# DC_link_input.net
KiCad netlist of a schematic drawn in Altium Designer
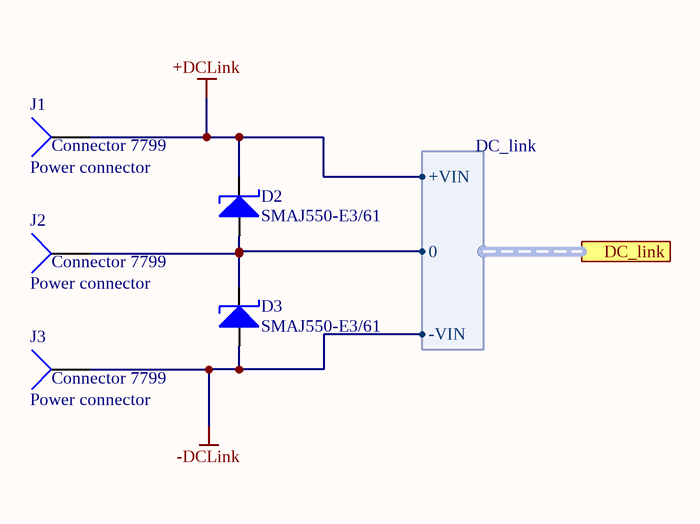
[diagram p0: DC_link_input.SchDoc]

(export (version "E")
  (design (tool "Eeschema 10.0.6"))
  (components
    (comp (ref "D2")
      (value "SMAJ550-E3/61")
      (footprint "DO 214")
      (description "TVS DIODE 495V 760V DO214AC")
      (libsource (lib "EdgeInverter_library") (part "SMAJ550-E3/61"))
    )
    (comp (ref "D3")
      (value "SMAJ550-E3/61")
      (footprint "DO 214")
      (description "TVS DIODE 495V 760V DO214AC")
      (libsource (lib "EdgeInverter_library") (part "SMAJ550-E3/61"))
    )
    (comp (ref "J1")
      (value "Power connector")
      (footprint "7799 Power Connector")
      (description "TERM SCREW M4 6 PIN PCB")
      (fields (field (name "ALTIUM_VALUE") "Connector 7799"))
      (libsource (lib "EdgeInverter_library") (part "Power connector"))
    )
    (comp (ref "J2")
      (value "Power connector")
      (footprint "7799 Power Connector")
      (description "TERM SCREW M4 6 PIN PCB")
      (fields (field (name "ALTIUM_VALUE") "Connector 7799"))
      (libsource (lib "EdgeInverter_library") (part "Power connector"))
    )
    (comp (ref "J3")
      (value "Power connector")
      (footprint "7799 Power Connector")
      (description "TERM SCREW M4 6 PIN PCB")
      (fields (field (name "ALTIUM_VALUE") "Connector 7799"))
      (libsource (lib "EdgeInverter_library") (part "Power connector"))
    )
  )
  (nets
    (net (code "2") (name "+DCLink") (class "Default")
      (node (ref "D2") (pin "2") (pinfunction "2_2") (pintype "passive"))
      (node (ref "J1") (pin "1") (pinfunction "1_1") (pintype "power_in"))
    )
    (net (code "3") (name "-DCLink") (class "Default")
      (node (ref "D3") (pin "1") (pinfunction "1_1") (pintype "passive"))
      (node (ref "J3") (pin "1") (pinfunction "1_1") (pintype "power_in"))
    )
    (net (code "5") (name "Net-(D2-Pad1)") (class "Default")
      (node (ref "D2") (pin "1") (pinfunction "1_1") (pintype "passive"))
      (node (ref "D3") (pin "2") (pinfunction "2_2") (pintype "passive"))
      (node (ref "J2") (pin "1") (pinfunction "1_1") (pintype "power_in"))
    )
  )
)
